# RFSOC_SAWG_Mezzanine.net
KiCad netlist of a schematic drawn in Altium Designer
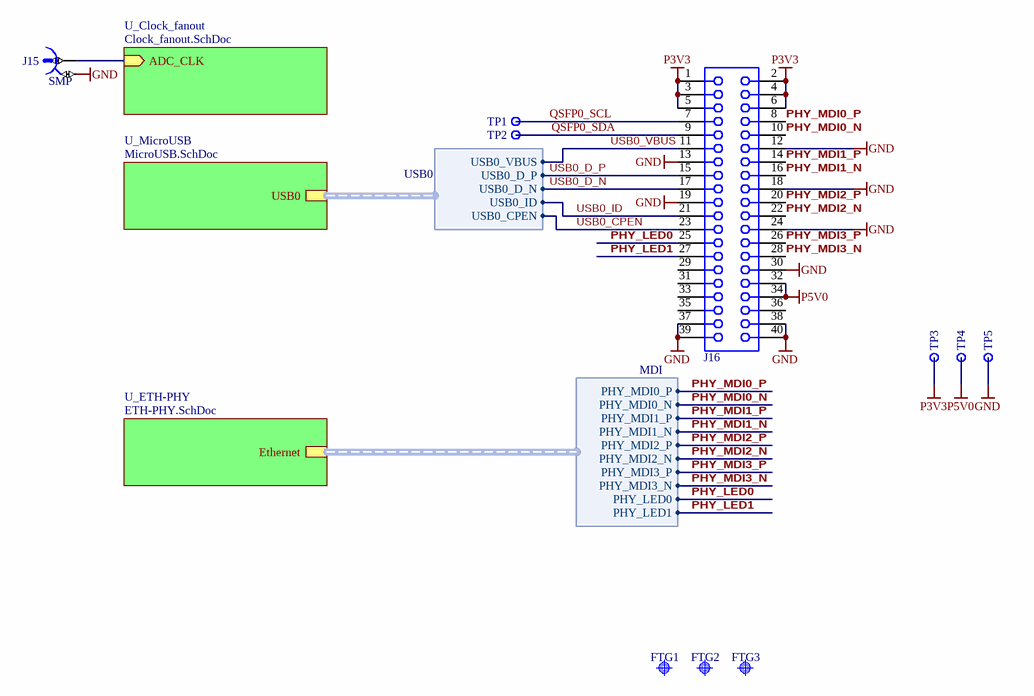
[diagram p0: RFSOC_SAWG_Mezzanine.SchDoc]

(export (version "E")
  (design (tool "Eeschema 10.0.6"))
  (components
    (comp (ref "FTG1")
      (value "Use only in PCB")
      (footprint "FIDUCIAL_TOP_S100-200")
      (description "Fiducial Target")
      (fields (field (name "PART NUMBER") "FIDUCIAL_TARGET_S100-200") (field (name "AUTHOR") "CERN DEM JLC"))
      (libsource (lib "Eletro-mechanical") (part "Fiducial Target"))
    )
    (comp (ref "FTG2")
      (value "Use only in PCB")
      (footprint "FIDUCIAL_TOP_S100-200")
      (description "Fiducial Target")
      (fields (field (name "PART NUMBER") "FIDUCIAL_TARGET_S100-200") (field (name "AUTHOR") "CERN DEM JLC"))
      (libsource (lib "Eletro-mechanical") (part "Fiducial Target"))
    )
    (comp (ref "FTG3")
      (value "Use only in PCB")
      (footprint "FIDUCIAL_TOP_S100-200")
      (description "Fiducial Target")
      (fields (field (name "PART NUMBER") "FIDUCIAL_TARGET_S100-200") (field (name "AUTHOR") "CERN DEM JLC"))
      (libsource (lib "Eletro-mechanical") (part "Fiducial Target"))
    )
    (comp (ref "J15")
      (value "SMP")
      (footprint "AMPHENOL_302102")
      (fields
        (field (name "PART NUMBER") "AMPHENOL_302102")
        (field (name "MANUFACTURER") "AMPHENOL")
        (field (name "MANUFACTURER PART NUMBER") "302102")
        (field (name "AUTHOR") "CERN DEM MR")
      )
      (libsource (lib "Connectors") (part "Coax_1Male_1Shield"))
    )
    (comp (ref "J16")
      (value "658807713040")
      (footprint "658807713040")
      (description "WR-BTB Board to Board Connector, Female Receptacle, pitch 0.8mm, height 7.75mm, 40p")
      (fields (field (name "MANUFACTURER") "Wurth Elektronik"))
      (libsource (lib "Altium_WR-BTB (rev22a)") (part "658807713040"))
    )
    (comp (ref "TP1")
      (value "Test Point")
      (footprint "TPS127")
      (fields (field (name "PART NUMBER") "SMD_PAD_1.27X1.27MM") (field (name "AUTHOR") "CERN DEM JLC"))
      (libsource (lib "Eletro-mechanical") (part "Test Point"))
    )
    (comp (ref "TP2")
      (value "Test Point")
      (footprint "TPS127")
      (fields (field (name "PART NUMBER") "SMD_PAD_1.27X1.27MM") (field (name "AUTHOR") "CERN DEM JLC"))
      (libsource (lib "Eletro-mechanical") (part "Test Point"))
    )
    (comp (ref "TP3")
      (value "Test Point")
      (footprint "TPS127")
      (fields (field (name "PART NUMBER") "SMD_PAD_1.27X1.27MM") (field (name "AUTHOR") "CERN DEM JLC"))
      (libsource (lib "Eletro-mechanical") (part "Test Point"))
    )
    (comp (ref "TP4")
      (value "Test Point")
      (footprint "TPS127")
      (fields (field (name "PART NUMBER") "SMD_PAD_1.27X1.27MM") (field (name "AUTHOR") "CERN DEM JLC"))
      (libsource (lib "Eletro-mechanical") (part "Test Point"))
    )
    (comp (ref "TP5")
      (value "Test Point")
      (footprint "TPS127")
      (fields (field (name "PART NUMBER") "SMD_PAD_1.27X1.27MM") (field (name "AUTHOR") "CERN DEM JLC"))
      (libsource (lib "Eletro-mechanical") (part "Test Point"))
    )
  )
  (nets
    (net (code "3") (name "/ADC_CLK") (class "Default")
      (node (ref "J15") (pin "1") (pinfunction "1_1") (pintype "bidirectional"))
    )
    (net (code "4") (name "/PHY_LED0") (class "Default")
      (node (ref "J16") (pin "25") (pinfunction "25_25") (pintype "passive"))
    )
    (net (code "5") (name "/PHY_LED1") (class "Default")
      (node (ref "J16") (pin "27") (pinfunction "27_27") (pintype "passive"))
    )
    (net (code "6") (name "/PHY_MDI0_N") (class "Default")
      (node (ref "J16") (pin "10") (pinfunction "10_10") (pintype "passive"))
    )
    (net (code "7") (name "/PHY_MDI0_P") (class "Default")
      (node (ref "J16") (pin "8") (pinfunction "8_8") (pintype "passive"))
    )
    (net (code "8") (name "/PHY_MDI1_N") (class "Default")
      (node (ref "J16") (pin "16") (pinfunction "16_16") (pintype "passive"))
    )
    (net (code "9") (name "/PHY_MDI1_P") (class "Default")
      (node (ref "J16") (pin "14") (pinfunction "14_14") (pintype "passive"))
    )
    (net (code "10") (name "/PHY_MDI2_N") (class "Default")
      (node (ref "J16") (pin "22") (pinfunction "22_22") (pintype "passive"))
    )
    (net (code "11") (name "/PHY_MDI2_P") (class "Default")
      (node (ref "J16") (pin "20") (pinfunction "20_20") (pintype "passive"))
    )
    (net (code "12") (name "/PHY_MDI3_N") (class "Default")
      (node (ref "J16") (pin "28") (pinfunction "28_28") (pintype "passive"))
    )
    (net (code "13") (name "/PHY_MDI3_P") (class "Default")
      (node (ref "J16") (pin "26") (pinfunction "26_26") (pintype "passive"))
    )
    (net (code "14") (name "/QSFP0_SCL") (class "Default")
      (node (ref "J16") (pin "7") (pinfunction "7_7") (pintype "passive"))
      (node (ref "TP1") (pin "1") (pinfunction "1_1") (pintype "bidirectional"))
    )
    (net (code "15") (name "/QSFP0_SDA") (class "Default")
      (node (ref "J16") (pin "9") (pinfunction "9_9") (pintype "passive"))
      (node (ref "TP2") (pin "1") (pinfunction "1_1") (pintype "bidirectional"))
    )
    (net (code "16") (name "/USB0_CPEN") (class "Default")
      (node (ref "J16") (pin "23") (pinfunction "23_23") (pintype "passive"))
    )
    (net (code "17") (name "/USB0_D_N") (class "Default")
      (node (ref "J16") (pin "17") (pinfunction "17_17") (pintype "passive"))
    )
    (net (code "18") (name "/USB0_D_P") (class "Default")
      (node (ref "J16") (pin "15") (pinfunction "15_15") (pintype "passive"))
    )
    (net (code "19") (name "/USB0_ID") (class "Default")
      (node (ref "J16") (pin "21") (pinfunction "21_21") (pintype "passive"))
    )
    (net (code "20") (name "/USB0_VBUS") (class "Default")
      (node (ref "J16") (pin "11") (pinfunction "11_11") (pintype "passive"))
    )
    (net (code "23") (name "GND") (class "Default")
      (node (ref "J15") (pin "2") (pinfunction "2_2") (pintype "bidirectional"))
      (node (ref "J16") (pin "12") (pinfunction "12_12") (pintype "passive"))
      (node (ref "J16") (pin "13") (pinfunction "13_13") (pintype "passive"))
      (node (ref "J16") (pin "18") (pinfunction "18_18") (pintype "passive"))
      (node (ref "J16") (pin "19") (pinfunction "19_19") (pintype "passive"))
      (node (ref "J16") (pin "24") (pinfunction "24_24") (pintype "passive"))
      (node (ref "J16") (pin "30") (pinfunction "30_30") (pintype "passive"))
      (node (ref "J16") (pin "37") (pinfunction "37_37") (pintype "passive"))
      (node (ref "J16") (pin "38") (pinfunction "38_38") (pintype "passive"))
      (node (ref "J16") (pin "39") (pinfunction "39_39") (pintype "passive"))
      (node (ref "J16") (pin "40") (pinfunction "40_40") (pintype "passive"))
      (node (ref "TP5") (pin "1") (pinfunction "1_1") (pintype "bidirectional"))
    )
    (net (code "24") (name "P3V3") (class "Default")
      (node (ref "J16") (pin "1") (pinfunction "1_1") (pintype "passive"))
      (node (ref "J16") (pin "2") (pinfunction "2_2") (pintype "passive"))
      (node (ref "J16") (pin "3") (pinfunction "3_3") (pintype "passive"))
      (node (ref "J16") (pin "4") (pinfunction "4_4") (pintype "passive"))
      (node (ref "J16") (pin "5") (pinfunction "5_5") (pintype "passive"))
      (node (ref "J16") (pin "6") (pinfunction "6_6") (pintype "passive"))
      (node (ref "TP3") (pin "1") (pinfunction "1_1") (pintype "bidirectional"))
    )
    (net (code "25") (name "P5V0") (class "Default")
      (node (ref "J16") (pin "32") (pinfunction "32_32") (pintype "passive"))
      (node (ref "J16") (pin "34") (pinfunction "34_34") (pintype "passive"))
      (node (ref "TP4") (pin "1") (pinfunction "1_1") (pintype "bidirectional"))
    )
    (net (code "26") (name "unconnected-(J16-Pad29)") (class "Default")
      (node (ref "J16") (pin "29") (pinfunction "29_29") (pintype "passive"))
    )
    (net (code "27") (name "unconnected-(J16-Pad31)") (class "Default")
      (node (ref "J16") (pin "31") (pinfunction "31_31") (pintype "passive"))
    )
    (net (code "28") (name "unconnected-(J16-Pad33)") (class "Default")
      (node (ref "J16") (pin "33") (pinfunction "33_33") (pintype "passive"))
    )
    (net (code "29") (name "unconnected-(J16-Pad35)") (class "Default")
      (node (ref "J16") (pin "35") (pinfunction "35_35") (pintype "passive"))
    )
    (net (code "30") (name "unconnected-(J16-Pad36)") (class "Default")
      (node (ref "J16") (pin "36") (pinfunction "36_36") (pintype "passive"))
    )
  )
)
